# hair_comb.net
KiCad netlist of a schematic drawn in EAGLE
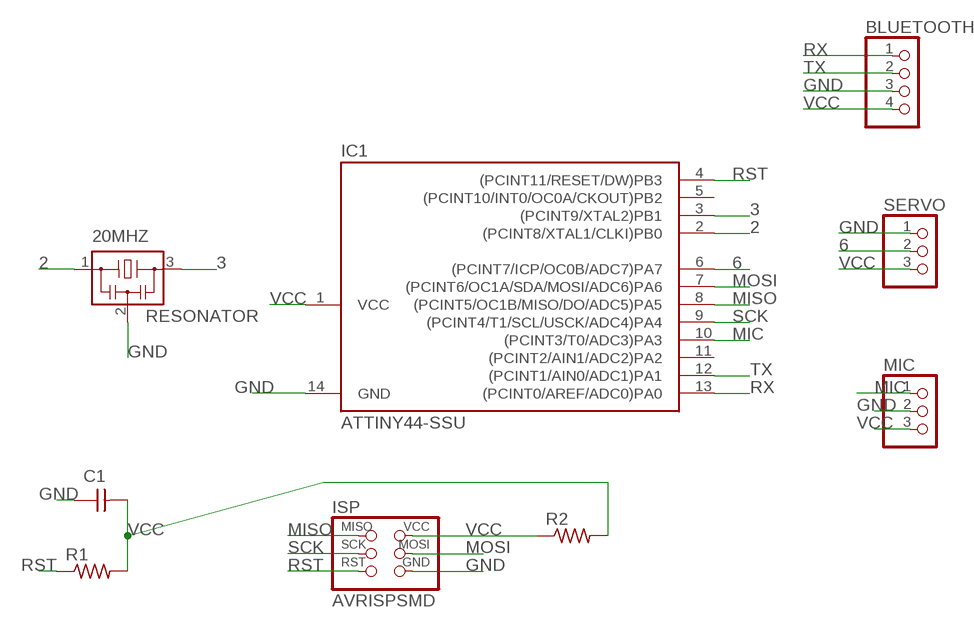
[diagram p0: schematic, sheet 1]

(export (version "E")
  (design (tool "Eeschema 10.0.6"))
  (components
    (comp (ref "20MHZ")
      (value "RESONATOR")
      (footprint "eagle-import:EFOBM")
      (libsource (lib "eagle-import") (part "RESONATOR"))
    )
    (comp (ref "BLUETOOTH")
      (value "PINHD-1X4/90")
      (footprint "eagle-import:1X04_90")
      (libsource (lib "eagle-import") (part "PINHD-1X4/90"))
    )
    (comp (ref "C1")
      (value "CAP-UNPOLARIZEDFAB")
      (footprint "eagle-import:C1206FAB")
      (libsource (lib "eagle-import") (part "CAP-UNPOLARIZEDFAB"))
    )
    (comp (ref "IC1")
      (value "ATTINY44-SSU")
      (footprint "eagle-import:SOIC14")
      (libsource (lib "eagle-import") (part "ATTINY44-SSU"))
    )
    (comp (ref "ISP")
      (value "AVRISPSMD")
      (footprint "eagle-import:2X03SMD")
      (libsource (lib "eagle-import") (part "AVRISPSMD"))
    )
    (comp (ref "MIC")
      (value "PINHD-1X3/90")
      (footprint "eagle-import:1X03_90")
      (libsource (lib "eagle-import") (part "PINHD-1X3/90"))
    )
    (comp (ref "R1")
      (value "RES-US1206FAB")
      (footprint "eagle-import:R1206FAB")
      (libsource (lib "eagle-import") (part "RES-US1206FAB"))
    )
    (comp (ref "R2")
      (value "RES-US1206FAB")
      (footprint "eagle-import:R1206FAB")
      (libsource (lib "eagle-import") (part "RES-US1206FAB"))
    )
    (comp (ref "SERVO")
      (value "PINHD-1X3/90")
      (footprint "eagle-import:1X03_90")
      (libsource (lib "eagle-import") (part "PINHD-1X3/90"))
    )
  )
  (nets
    (net (code "1") (name "/2") (class "Default")
      (node (ref "20MHZ") (pin "1") (pinfunction "1_1") (pintype "passive"))
      (node (ref "IC1") (pin "2") (pinfunction "(PCINT8/XTAL1/CLKI)PB0_2") (pintype "bidirectional"))
    )
    (net (code "2") (name "/3") (class "Default")
      (node (ref "20MHZ") (pin "3") (pinfunction "3_3") (pintype "passive"))
      (node (ref "IC1") (pin "3") (pinfunction "(PCINT9/XTAL2)PB1_3") (pintype "bidirectional"))
    )
    (net (code "3") (name "/6") (class "Default")
      (node (ref "IC1") (pin "6") (pinfunction "(PCINT7/ICP/OC0B/ADC7)PA7_6") (pintype "bidirectional"))
      (node (ref "SERVO") (pin "2") (pinfunction "2_2") (pintype "passive"))
    )
    (net (code "4") (name "/GND") (class "Default")
      (node (ref "20MHZ") (pin "2") (pinfunction "2_2") (pintype "passive"))
      (node (ref "BLUETOOTH") (pin "3") (pinfunction "3_3") (pintype "passive"))
      (node (ref "C1") (pin "1") (pinfunction "1_1") (pintype "passive"))
      (node (ref "IC1") (pin "14") (pinfunction "GND_14") (pintype "power_in"))
      (node (ref "ISP") (pin "6") (pinfunction "GND_6") (pintype "passive"))
      (node (ref "MIC") (pin "2") (pinfunction "2_2") (pintype "passive"))
      (node (ref "SERVO") (pin "1") (pinfunction "1_1") (pintype "passive"))
    )
    (net (code "5") (name "/MIC") (class "Default")
      (node (ref "IC1") (pin "10") (pinfunction "(PCINT3/T0/ADC3)PA3_10") (pintype "bidirectional"))
      (node (ref "MIC") (pin "1") (pinfunction "1_1") (pintype "passive"))
    )
    (net (code "6") (name "/MISO") (class "Default")
      (node (ref "IC1") (pin "8") (pinfunction "(PCINT5/OC1B/MISO/DO/ADC5)PA5_8") (pintype "bidirectional"))
      (node (ref "ISP") (pin "1") (pinfunction "MISO_1") (pintype "passive"))
    )
    (net (code "7") (name "/MOSI") (class "Default")
      (node (ref "IC1") (pin "7") (pinfunction "(PCINT6/OC1A/SDA/MOSI/ADC6)PA6_7") (pintype "bidirectional"))
      (node (ref "ISP") (pin "4") (pinfunction "MOSI_4") (pintype "passive"))
    )
    (net (code "8") (name "/RST") (class "Default")
      (node (ref "IC1") (pin "4") (pinfunction "(PCINT11/RESET/DW)PB3_4") (pintype "bidirectional"))
      (node (ref "ISP") (pin "5") (pinfunction "RST_5") (pintype "passive"))
      (node (ref "R1") (pin "1") (pinfunction "1_1") (pintype "passive"))
    )
    (net (code "9") (name "/RX") (class "Default")
      (node (ref "BLUETOOTH") (pin "1") (pinfunction "1_1") (pintype "passive"))
      (node (ref "IC1") (pin "13") (pinfunction "(PCINT0/AREF/ADC0)PA0_13") (pintype "bidirectional"))
    )
    (net (code "10") (name "/SCK") (class "Default")
      (node (ref "IC1") (pin "9") (pinfunction "(PCINT4/T1/SCL/USCK/ADC4)PA4_9") (pintype "bidirectional"))
      (node (ref "ISP") (pin "3") (pinfunction "SCK_3") (pintype "passive"))
    )
    (net (code "11") (name "/TX") (class "Default")
      (node (ref "BLUETOOTH") (pin "2") (pinfunction "2_2") (pintype "passive"))
      (node (ref "IC1") (pin "12") (pinfunction "(PCINT1/AIN0/ADC1)PA1_12") (pintype "bidirectional"))
    )
    (net (code "12") (name "/VCC") (class "Default")
      (node (ref "BLUETOOTH") (pin "4") (pinfunction "4_4") (pintype "passive"))
      (node (ref "C1") (pin "2") (pinfunction "2_2") (pintype "passive"))
      (node (ref "IC1") (pin "1") (pinfunction "VCC_1") (pintype "power_in"))
      (node (ref "ISP") (pin "2") (pinfunction "VCC_2") (pintype "passive"))
      (node (ref "MIC") (pin "3") (pinfunction "3_3") (pintype "passive"))
      (node (ref "R1") (pin "2") (pinfunction "2_2") (pintype "passive"))
      (node (ref "R2") (pin "1") (pinfunction "1_1") (pintype "passive"))
      (node (ref "R2") (pin "2") (pinfunction "2_2") (pintype "passive"))
      (node (ref "SERVO") (pin "3") (pinfunction "3_3") (pintype "passive"))
    )
    (net (code "13") (name "unconnected-(IC1-(PCINT2{slash}AIN1{slash}ADC2)PA2-Pad11)") (class "Default")
      (node (ref "IC1") (pin "11") (pinfunction "(PCINT2/AIN1/ADC2)PA2_11") (pintype "bidirectional"))
    )
    (net (code "14") (name "unconnected-(IC1-(PCINT10{slash}INT0{slash}OC0A{slash}CKOUT)PB2-Pad5)") (class "Default")
      (node (ref "IC1") (pin "5") (pinfunction "(PCINT10/INT0/OC0A/CKOUT)PB2_5") (pintype "bidirectional"))
    )
  )
)
